# POWER.net
KiCad netlist of a schematic drawn in Altium Designer
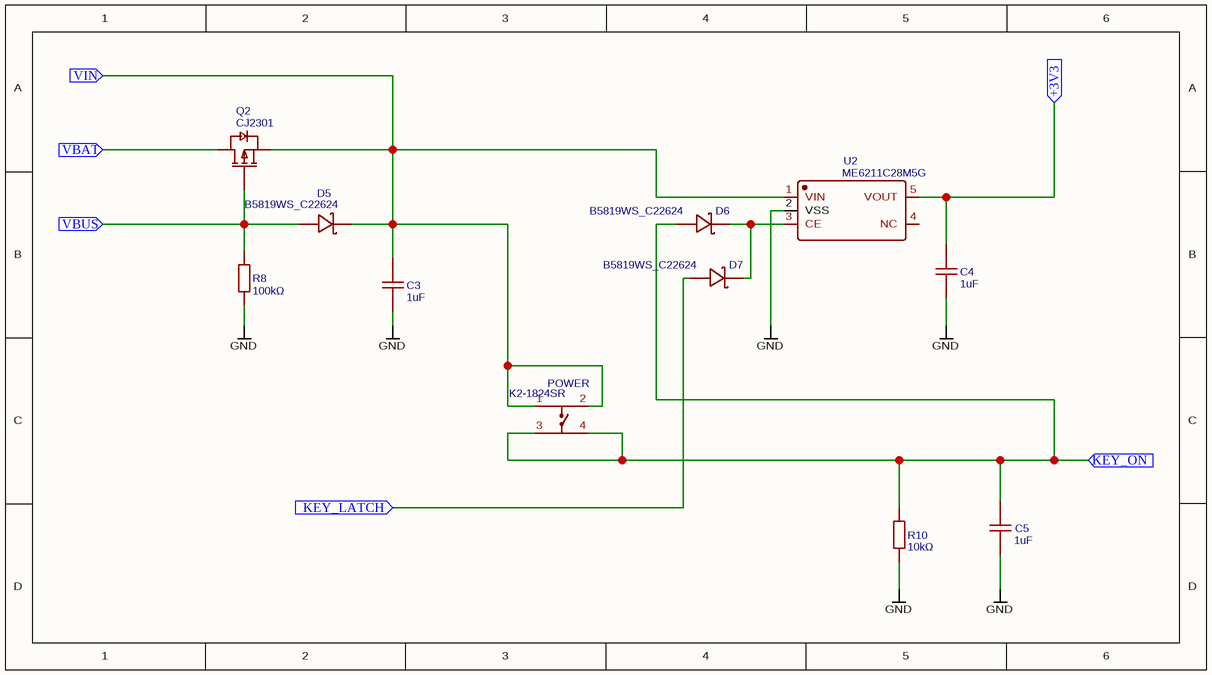
[diagram p0: POWER.schdoc]

(export (version "E")
  (design (tool "Eeschema 10.0.6"))
  (components
    (comp (ref "C3")
      (value "1uF")
      (fields
        (field (name "BOM_MANUFACTURER PART") "0603B105K160NT")
        (field (name "BOM_SUPPLIER PART") "C93816")
      )
      (libsource (lib "altium-import") (part "root_1_1uF_"))
    )
    (comp (ref "C4")
      (value "1uF")
      (fields
        (field (name "BOM_MANUFACTURER PART") "0603B105K160NT")
        (field (name "BOM_SUPPLIER PART") "C93816")
      )
      (libsource (lib "altium-import") (part "root_1_1uF_"))
    )
    (comp (ref "C5")
      (value "1uF")
      (fields
        (field (name "BOM_MANUFACTURER PART") "0603B105K160NT")
        (field (name "BOM_SUPPLIER PART") "C93816")
      )
      (libsource (lib "altium-import") (part "root_1_1uF_"))
    )
    (comp (ref "D5")
      (value "B5819WS_C22624")
      (fields (field (name "BOM_MANUFACTURER PART") "B5819WS") (field (name "BOM_SUPPLIER PART") "C22624"))
      (libsource (lib "altium-import") (part "root_2_B5819WS_C22624_"))
    )
    (comp (ref "D6")
      (value "B5819WS_C22624")
      (fields (field (name "BOM_MANUFACTURER PART") "B5819WS") (field (name "BOM_SUPPLIER PART") "C22624"))
      (libsource (lib "altium-import") (part "root_2_B5819WS_C22624_"))
    )
    (comp (ref "D7")
      (value "B5819WS_C22624")
      (fields (field (name "BOM_MANUFACTURER PART") "B5819WS") (field (name "BOM_SUPPLIER PART") "C22624"))
      (libsource (lib "altium-import") (part "root_2_B5819WS_C22624_"))
    )
    (comp (ref "POWER")
      (value "K2-1824SR")
      (fields
        (field (name "BOM_MANUFACTURER PART") "K2-1824SR-B4SW-06")
        (field (name "BOM_SUPPLIER PART") "C128938")
        (field (name "CONTRIBUTOR") "LCSC")
      )
      (libsource (lib "altium-import") (part "root_0_K2-1824SR_"))
    )
    (comp (ref "Q2")
      (value "CJ2301")
      (fields (field (name "BOM_SUPPLIER PART") "C2910170") (field (name "CONTRIBUTOR") "LCSC"))
      (libsource (lib "altium-import") (part "root_1_CJ2301_"))
    )
    (comp (ref "R8")
      (value "100kΩ")
      (fields
        (field (name "BOM_MANUFACTURER PART") "RS-03K1003FT")
        (field (name "BOM_SUPPLIER PART") "C115320")
        (field (name "CONTRIBUTOR") "LCSC")
      )
      (libsource (lib "altium-import") (part "root_1_100kΩ_"))
    )
    (comp (ref "R10")
      (value "10kΩ")
      (fields
        (field (name "BOM_SUPPLIER PART") "C115324")
        (field (name "BOM_MANUFACTURER PART") "RS-03K1002FT")
        (field (name "CONTRIBUTOR") "LCSC")
      )
      (libsource (lib "altium-import") (part "root_1_10kΩ_"))
    )
    (comp (ref "U2")
      (value "ME6211C28M5G")
      (fields
        (field (name "BOM_MANUFACTURER PART") "ME6211C33M5G-N")
        (field (name "BOM_SUPPLIER PART") "C82942")
      )
      (libsource (lib "altium-import") (part "root_0_ME6211C28M5G_"))
    )
  )
  (nets
    (net (code "1") (name "/+3V3") (class "Default")
      (node (ref "C4") (pin "2") (pinfunction "2_2") (pintype "passive"))
      (node (ref "U2") (pin "5") (pinfunction "VOUT_5") (pintype "passive"))
    )
    (net (code "2") (name "/KEY_LATCH") (class "Default")
      (node (ref "D7") (pin "2") (pinfunction "A_2") (pintype "passive"))
    )
    (net (code "3") (name "/KEY_ON") (class "Default")
      (node (ref "C5") (pin "2") (pinfunction "2_2") (pintype "passive"))
      (node (ref "D6") (pin "2") (pinfunction "A_2") (pintype "passive"))
      (node (ref "POWER") (pin "3") (pinfunction "3_3") (pintype "passive"))
      (node (ref "POWER") (pin "4") (pinfunction "4_4") (pintype "passive"))
      (node (ref "R10") (pin "2") (pinfunction "2_2") (pintype "passive"))
    )
    (net (code "4") (name "/VBAT") (class "Default")
      (node (ref "Q2") (pin "3") (pinfunction "D_3") (pintype "passive"))
    )
    (net (code "5") (name "/VBUS") (class "Default")
      (node (ref "D5") (pin "2") (pinfunction "A_2") (pintype "passive"))
      (node (ref "Q2") (pin "1") (pinfunction "G_1") (pintype "passive"))
      (node (ref "R8") (pin "2") (pinfunction "2_2") (pintype "passive"))
    )
    (net (code "6") (name "/VIN") (class "Default")
      (node (ref "C3") (pin "2") (pinfunction "2_2") (pintype "passive"))
      (node (ref "D5") (pin "1") (pinfunction "K_1") (pintype "passive"))
      (node (ref "POWER") (pin "1") (pinfunction "1_1") (pintype "passive"))
      (node (ref "POWER") (pin "2") (pinfunction "2_2") (pintype "passive"))
      (node (ref "Q2") (pin "2") (pinfunction "S_2") (pintype "passive"))
      (node (ref "U2") (pin "1") (pinfunction "VIN_1") (pintype "passive"))
    )
    (net (code "7") (name "GND") (class "Default")
      (node (ref "C3") (pin "1") (pinfunction "1_1") (pintype "passive"))
      (node (ref "C4") (pin "1") (pinfunction "1_1") (pintype "passive"))
      (node (ref "C5") (pin "1") (pinfunction "1_1") (pintype "passive"))
      (node (ref "R10") (pin "1") (pinfunction "1_1") (pintype "passive"))
      (node (ref "R8") (pin "1") (pinfunction "1_1") (pintype "passive"))
      (node (ref "U2") (pin "2") (pinfunction "VSS_2") (pintype "passive"))
    )
    (net (code "8") (name "Net-(D6-K)") (class "Default")
      (node (ref "D6") (pin "1") (pinfunction "K_1") (pintype "passive"))
      (node (ref "D7") (pin "1") (pinfunction "K_1") (pintype "passive"))
      (node (ref "U2") (pin "3") (pinfunction "CE_3") (pintype "passive"))
    )
    (net (code "9") (name "unconnected-(U2-NC-Pad4)") (class "Default")
      (node (ref "U2") (pin "4") (pinfunction "NC_4") (pintype "passive"))
    )
  )
)
